# SCH_Astraeus_I_2023-09-04.net
KiCad netlist of a schematic drawn in EasyEDA
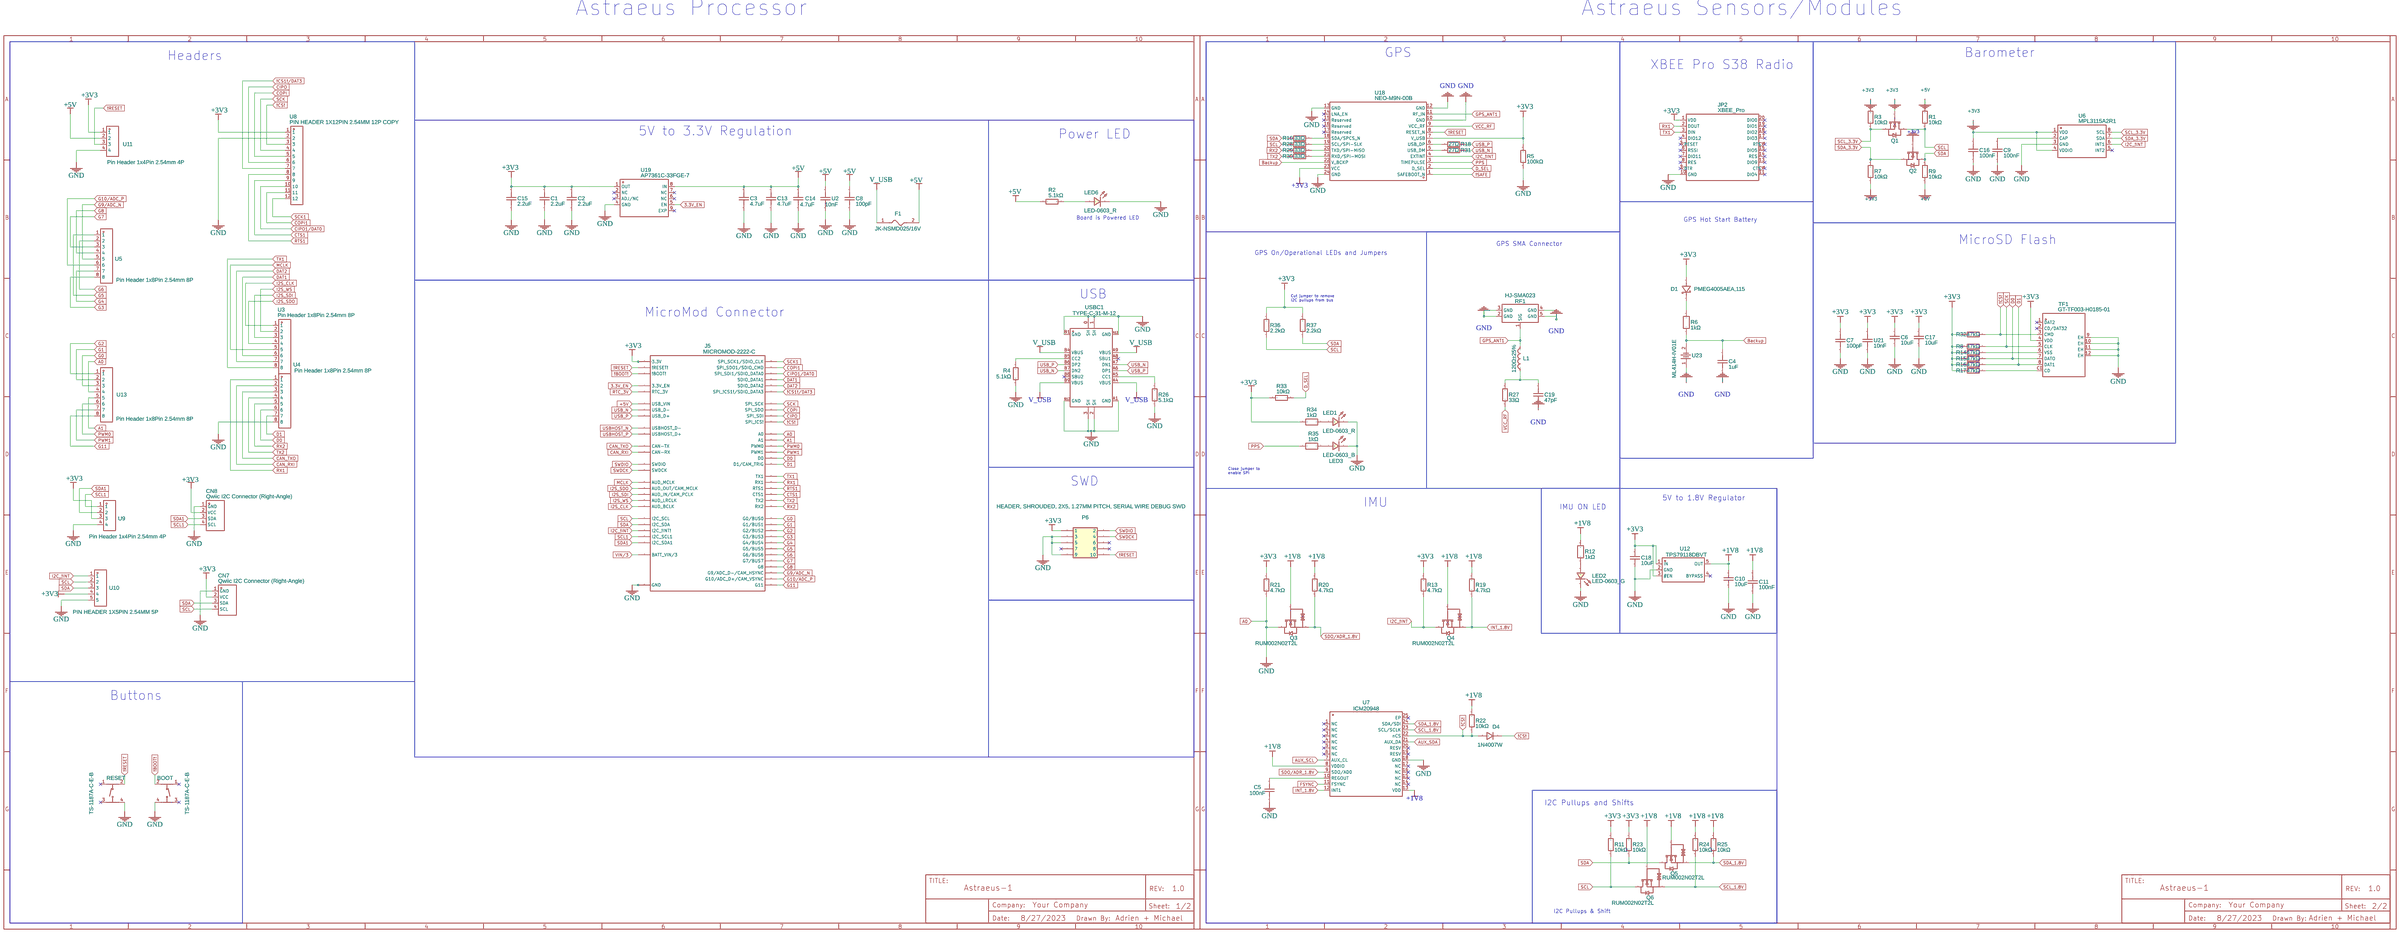
[diagram p0: schematic sheet]

(export (version "E")
  (design (tool "Eeschema 10.0.6"))
  (components
    (comp (ref "BOOT")
      (value "TS-1187A-C-E-B")
      (fields (field (name "Manufacturer") "XKB Connectivity(中国星坤)"))
      (libsource (lib "") (part "TS-1187A-C-E-B"))
    )
    (comp (ref "C1")
      (value "2.2uF")
      (fields
        (field (name "Manufacturer Part") "TCC0603X5R225K250CT")
        (field (name "Manufacturer") "CCTC(三环)")
      )
      (libsource (lib "") (part "TCC0603X5R225K250CT"))
    )
    (comp (ref "C2")
      (value "2.2uF")
      (fields
        (field (name "Manufacturer Part") "TCC0603X5R225K250CT")
        (field (name "Manufacturer") "CCTC(三环)")
      )
      (libsource (lib "") (part "TCC0603X5R225K250CT"))
    )
    (comp (ref "C3")
      (value "4.7uF")
      (fields
        (field (name "Manufacturer Part") "V475K0603X7R6R3NET")
        (field (name "Manufacturer") "VIIYONG(微容)")
      )
      (libsource (lib "") (part "V475K0603X7R6R3NET"))
    )
    (comp (ref "C4")
      (value "1uF")
      (fields (field (name "Manufacturer Part") "0603X105J160CT") (field (name "Manufacturer") "Walsin(华新科)"))
      (libsource (lib "") (part "0603X105J160CT"))
    )
    (comp (ref "C5")
      (value "100nF")
      (fields (field (name "Manufacturer Part") "0603ZC104KAT2A") (field (name "Manufacturer") "Kyocera AVX"))
      (libsource (lib "") (part "0603ZC104KAT2A"))
    )
    (comp (ref "C6")
      (value "10uF")
      (fields
        (field (name "Manufacturer Part") "CC0603MRX5R7BB106")
        (field (name "Manufacturer") "YAGEO(国巨)")
      )
      (libsource (lib "") (part "CC0603MRX5R7BB106"))
    )
    (comp (ref "C7")
      (value "100pF")
      (fields
        (field (name "Manufacturer Part") "TCC0603COG101J500CT")
        (field (name "Manufacturer") "CCTC(三环)")
      )
      (libsource (lib "") (part "TCC0603COG101J500CT"))
    )
    (comp (ref "C8")
      (value "100pF")
      (fields
        (field (name "Manufacturer Part") "TCC0603COG101J500CT")
        (field (name "Manufacturer") "CCTC(三环)")
      )
      (libsource (lib "") (part "TCC0603COG101J500CT"))
    )
    (comp (ref "C9")
      (value "100nF")
      (fields (field (name "Manufacturer Part") "0603ZC104KAT2A") (field (name "Manufacturer") "Kyocera AVX"))
      (libsource (lib "") (part "0603ZC104KAT2A"))
    )
    (comp (ref "C10")
      (value "10uF")
      (fields
        (field (name "Manufacturer Part") "CC0603MRX5R7BB106")
        (field (name "Manufacturer") "YAGEO(国巨)")
      )
      (libsource (lib "") (part "CC0603MRX5R7BB106"))
    )
    (comp (ref "C11")
      (value "100nF")
      (fields (field (name "Manufacturer Part") "0603ZC104KAT2A") (field (name "Manufacturer") "Kyocera AVX"))
      (libsource (lib "") (part "0603ZC104KAT2A"))
    )
    (comp (ref "C13")
      (value "4.7uF")
      (fields
        (field (name "Manufacturer Part") "V475K0603X7R6R3NET")
        (field (name "Manufacturer") "VIIYONG(微容)")
      )
      (libsource (lib "") (part "V475K0603X7R6R3NET"))
    )
    (comp (ref "C14")
      (value "4.7uF")
      (fields
        (field (name "Manufacturer Part") "V475K0603X7R6R3NET")
        (field (name "Manufacturer") "VIIYONG(微容)")
      )
      (libsource (lib "") (part "V475K0603X7R6R3NET"))
    )
    (comp (ref "C15")
      (value "2.2uF")
      (fields
        (field (name "Manufacturer Part") "TCC0603X5R225K250CT")
        (field (name "Manufacturer") "CCTC(三环)")
      )
      (libsource (lib "") (part "TCC0603X5R225K250CT"))
    )
    (comp (ref "C16")
      (value "100nF")
      (fields (field (name "Manufacturer Part") "0603ZC104KAT2A") (field (name "Manufacturer") "Kyocera AVX"))
      (libsource (lib "") (part "0603ZC104KAT2A"))
    )
    (comp (ref "C17")
      (value "10uF")
      (fields
        (field (name "Manufacturer Part") "CC0603MRX5R7BB106")
        (field (name "Manufacturer") "YAGEO(国巨)")
      )
      (libsource (lib "") (part "CC0603MRX5R7BB106"))
    )
    (comp (ref "C18")
      (value "10uF")
      (fields
        (field (name "Manufacturer Part") "CC0603MRX5R7BB106")
        (field (name "Manufacturer") "YAGEO(国巨)")
      )
      (libsource (lib "") (part "CC0603MRX5R7BB106"))
    )
    (comp (ref "C19")
      (value "47pF")
      (fields (field (name "Manufacturer Part") "0603CG470G500NT") (field (name "Manufacturer") "FH(风华)"))
      (libsource (lib "") (part "0603CG470G500NT"))
    )
    (comp (ref "CN7")
      (value "Qwiic I2C Connector (Right-Angle)")
      (libsource (lib "") (part "Qwiic I2C Connector (Right-Angle)"))
    )
    (comp (ref "CN8")
      (value "Qwiic I2C Connector (Right-Angle)")
      (libsource (lib "") (part "Qwiic I2C Connector (Right-Angle)"))
    )
    (comp (ref "D1")
      (value "PMEG4005AEA,115")
      (fields (field (name "Manufacturer") "Nexperia(安世)"))
      (libsource (lib "") (part "PMEG4005AEA,115"))
    )
    (comp (ref "D4")
      (value "1N4007W")
      (fields (field (name "Manufacturer") "BLUE ROCKET"))
      (libsource (lib "") (part "1N4007W"))
    )
    (comp (ref "F1")
      (value "JK-NSMD025/16V")
      (fields (field (name "Manufacturer Part") "JK-nSMD025/16V") (field (name "Manufacturer") "JK(金科)"))
      (libsource (lib "") (part "JK-NSMD025/16V"))
    )
    (comp (ref "J5") (value "MICROMOD-2222-C") (libsource (lib "") (part "MICROMOD-2222-C")))
    (comp (ref "JP2") (value "XBEE_Pro") (libsource (lib "") (part "XBEE_Pro")))
    (comp (ref "L1")
      (value "120Ω±25%")
      (fields (field (name "Manufacturer Part") "BLM18KG121TN1D") (field (name "Manufacturer") "muRata(村田)"))
      (libsource (lib "") (part "BLM18KG121TN1D"))
    )
    (comp (ref "LED1")
      (value "LED-0603_R")
      (fields
        (field (name "Manufacturer Part") "19-217/R6C-AL1M2VY/3T")
        (field (name "Manufacturer") "EVERLIGHT(台湾亿光)")
      )
      (libsource (lib "") (part "LED-0603_R"))
    )
    (comp (ref "LED2")
      (value "LED-0603_G")
      (fields
        (field (name "Manufacturer Part") "19-217/GHC-YR1S2/3T")
        (field (name "Manufacturer") "EVERLIGHT(台湾亿光)")
      )
      (libsource (lib "") (part "LED-0603_G"))
    )
    (comp (ref "LED3")
      (value "LED-0603_B")
      (fields
        (field (name "Manufacturer Part") "19-217/BHC-ZL1M2RY/3T")
        (field (name "Manufacturer") "EVERLIGHT(台湾亿光)")
      )
      (libsource (lib "") (part "LED-0603_B"))
    )
    (comp (ref "LED6")
      (value "LED-0603_R")
      (fields
        (field (name "Manufacturer Part") "19-217/R6C-AL1M2VY/3T")
        (field (name "Manufacturer") "EVERLIGHT(台湾亿光)")
      )
      (libsource (lib "") (part "LED-0603_R"))
    )
    (comp (ref "P6")
      (value "HEADER, SHROUDED, 2X5, 1.27MM PITCH, SERIAL WIRE DEBUG SWD")
      (fields (field (name "Manufacturer Part") "3220-10-0100-00") (field (name "Manufacturer") "CNC Tech"))
      (libsource (lib "") (part "HEADER, SHROUDED, 2X5, 1.27MM PITCH, SERIAL WIRE DEBUG SWD"))
    )
    (comp (ref "Q1")
      (value "BSS138_C489349")
      (fields (field (name "Manufacturer Part") "BSS138") (field (name "Manufacturer") "KEXIN(科信)"))
      (libsource (lib "") (part "BSS138_C489349"))
    )
    (comp (ref "Q2")
      (value "BSS138_C489349")
      (fields (field (name "Manufacturer Part") "BSS138") (field (name "Manufacturer") "KEXIN(科信)"))
      (libsource (lib "") (part "BSS138_C489349"))
    )
    (comp (ref "Q3")
      (value "RUM002N02T2L")
      (fields (field (name "Manufacturer") "ROHM(罗姆)"))
      (libsource (lib "") (part "RUM002N02T2L"))
    )
    (comp (ref "Q4")
      (value "RUM002N02T2L")
      (fields (field (name "Manufacturer") "ROHM(罗姆)"))
      (libsource (lib "") (part "RUM002N02T2L"))
    )
    (comp (ref "Q5")
      (value "RUM002N02T2L")
      (fields (field (name "Manufacturer") "ROHM(罗姆)"))
      (libsource (lib "") (part "RUM002N02T2L"))
    )
    (comp (ref "Q6")
      (value "RUM002N02T2L")
      (fields (field (name "Manufacturer") "ROHM(罗姆)"))
      (libsource (lib "") (part "RUM002N02T2L"))
    )
    (comp (ref "R1")
      (value "10kΩ")
      (fields (field (name "Manufacturer Part") "RMC060310K5%N") (field (name "Manufacturer") "Tyohm(幸亚电阻)"))
      (libsource (lib "") (part "RMC060310K5%N_1"))
    )
    (comp (ref "R2")
      (value "5.1kΩ")
      (fields (field (name "Manufacturer Part") "RMC06035.1K5%N") (field (name "Manufacturer") "Tyohm(幸亚电阻)"))
      (libsource (lib "") (part "RMC06035.1K5%N"))
    )
    (comp (ref "R3")
      (value "10kΩ")
      (fields (field (name "Manufacturer Part") "RMC060310K5%N") (field (name "Manufacturer") "Tyohm(幸亚电阻)"))
      (libsource (lib "") (part "RMC060310K5%N_1"))
    )
    (comp (ref "R4")
      (value "5.1kΩ")
      (fields (field (name "Manufacturer Part") "RMC06035.1K5%N") (field (name "Manufacturer") "Tyohm(幸亚电阻)"))
      (libsource (lib "") (part "RMC06035.1K5%N_1"))
    )
    (comp (ref "R5")
      (value "100kΩ")
      (fields (field (name "Manufacturer Part") "RT0603DRE07100KL") (field (name "Manufacturer") "YAGEO(国巨)"))
      (libsource (lib "") (part "RT0603DRE07100KL"))
    )
    (comp (ref "R6")
      (value "1kΩ")
      (fields (field (name "Manufacturer Part") "SCR0603J1K") (field (name "Manufacturer") "VO(翔胜)"))
      (libsource (lib "") (part "SCR0603J1K"))
    )
    (comp (ref "R7")
      (value "10kΩ")
      (fields (field (name "Manufacturer Part") "RMC060310K5%N") (field (name "Manufacturer") "Tyohm(幸亚电阻)"))
      (libsource (lib "") (part "RMC060310K5%N_1"))
    )
    (comp (ref "R8")
      (value "47kΩ")
      (fields (field (name "Manufacturer Part") "CR0603-FX-4702ELF") (field (name "Manufacturer") "BOURNS"))
      (libsource (lib "") (part "CR0603-FX-4702ELF"))
    )
    (comp (ref "R9")
      (value "10kΩ")
      (fields (field (name "Manufacturer Part") "RMC060310K5%N") (field (name "Manufacturer") "Tyohm(幸亚电阻)"))
      (libsource (lib "") (part "RMC060310K5%N_1"))
    )
    (comp (ref "R10")
      (value "33Ω")
      (fields (field (name "Manufacturer Part") "RC0603FR-0733RL") (field (name "Manufacturer") "YAGEO(国巨)"))
      (libsource (lib "") (part "RC0603FR-0733RL_2"))
    )
    (comp (ref "R11")
      (value "10kΩ")
      (fields (field (name "Manufacturer Part") "RMC060310K5%N") (field (name "Manufacturer") "Tyohm(幸亚电阻)"))
      (libsource (lib "") (part "RMC060310K5%N_1"))
    )
    (comp (ref "R12")
      (value "1kΩ")
      (fields (field (name "Manufacturer Part") "SCR0603J1K") (field (name "Manufacturer") "VO(翔胜)"))
      (libsource (lib "") (part "SCR0603J1K"))
    )
    (comp (ref "R13")
      (value "4.7kΩ")
      (fields (field (name "Manufacturer Part") "RMC06034K7FN") (field (name "Manufacturer") "Tyohm(幸亚电阻)"))
      (libsource (lib "") (part "RMC06034.7K1%N"))
    )
    (comp (ref "R14")
      (value "47kΩ")
      (fields (field (name "Manufacturer Part") "CR0603-FX-4702ELF") (field (name "Manufacturer") "BOURNS"))
      (libsource (lib "") (part "CR0603-FX-4702ELF"))
    )
    (comp (ref "R15")
      (value "47kΩ")
      (fields (field (name "Manufacturer Part") "CR0603-FX-4702ELF") (field (name "Manufacturer") "BOURNS"))
      (libsource (lib "") (part "CR0603-FX-4702ELF"))
    )
    (comp (ref "R16")
      (value "47kΩ")
      (fields (field (name "Manufacturer Part") "CR0603-FX-4702ELF") (field (name "Manufacturer") "BOURNS"))
      (libsource (lib "") (part "CR0603-FX-4702ELF"))
    )
    (comp (ref "R17")
      (value "47kΩ")
      (fields (field (name "Manufacturer Part") "CR0603-FX-4702ELF") (field (name "Manufacturer") "BOURNS"))
      (libsource (lib "") (part "CR0603-FX-4702ELF"))
    )
    (comp (ref "R18")
      (value "27Ω")
      (fields (field (name "Manufacturer Part") "CR0603FA27R0G") (field (name "Manufacturer") "LIZ(丽智电子)"))
      (libsource (lib "") (part "CR0603FA27R0G"))
    )
    (comp (ref "R19")
      (value "4.7kΩ")
      (fields (field (name "Manufacturer Part") "RMC06034K7FN") (field (name "Manufacturer") "Tyohm(幸亚电阻)"))
      (libsource (lib "") (part "RMC06034.7K1%N"))
    )
    (comp (ref "R20")
      (value "4.7kΩ")
      (fields (field (name "Manufacturer Part") "RMC06034K7FN") (field (name "Manufacturer") "Tyohm(幸亚电阻)"))
      (libsource (lib "") (part "RMC06034.7K1%N"))
    )
    (comp (ref "R21")
      (value "4.7kΩ")
      (fields (field (name "Manufacturer Part") "RMC06034K7FN") (field (name "Manufacturer") "Tyohm(幸亚电阻)"))
      (libsource (lib "") (part "RMC06034.7K1%N"))
    )
    (comp (ref "R22")
      (value "10kΩ")
      (fields (field (name "Manufacturer Part") "RMC060310K5%N") (field (name "Manufacturer") "Tyohm(幸亚电阻)"))
      (libsource (lib "") (part "RMC060310K5%N_1"))
    )
    (comp (ref "R23")
      (value "10kΩ")
      (fields (field (name "Manufacturer Part") "RMC060310K5%N") (field (name "Manufacturer") "Tyohm(幸亚电阻)"))
      (libsource (lib "") (part "RMC060310K5%N_1"))
    )
    (comp (ref "R24")
      (value "10kΩ")
      (fields (field (name "Manufacturer Part") "RMC060310K5%N") (field (name "Manufacturer") "Tyohm(幸亚电阻)"))
      (libsource (lib "") (part "RMC060310K5%N_1"))
    )
    (comp (ref "R25")
      (value "10kΩ")
      (fields (field (name "Manufacturer Part") "RMC060310K5%N") (field (name "Manufacturer") "Tyohm(幸亚电阻)"))
      (libsource (lib "") (part "RMC060310K5%N_1"))
    )
    (comp (ref "R26")
      (value "5.1kΩ")
      (fields (field (name "Manufacturer Part") "RMC06035.1K5%N") (field (name "Manufacturer") "Tyohm(幸亚电阻)"))
      (libsource (lib "") (part "RMC06035.1K5%N_2"))
    )
    (comp (ref "R27")
      (value "33Ω")
      (fields (field (name "Manufacturer Part") "RC0603FR-0733RL") (field (name "Manufacturer") "YAGEO(国巨)"))
      (libsource (lib "") (part "RC0603FR-0733RL_1"))
    )
    (comp (ref "R28")
      (value "33Ω")
      (fields (field (name "Manufacturer Part") "RC0603FR-0733RL") (field (name "Manufacturer") "YAGEO(国巨)"))
      (libsource (lib "") (part "RC0603FR-0733RL"))
    )
    (comp (ref "R29")
      (value "33Ω")
      (fields (field (name "Manufacturer Part") "RC0603FR-0733RL") (field (name "Manufacturer") "YAGEO(国巨)"))
      (libsource (lib "") (part "RC0603FR-0733RL"))
    )
    (comp (ref "R30")
      (value "33Ω")
      (fields (field (name "Manufacturer Part") "RC0603FR-0733RL") (field (name "Manufacturer") "YAGEO(国巨)"))
      (libsource (lib "") (part "RC0603FR-0733RL"))
    )
    (comp (ref "R31")
      (value "27Ω")
      (fields (field (name "Manufacturer Part") "CR0603FA27R0G") (field (name "Manufacturer") "LIZ(丽智电子)"))
      (libsource (lib "") (part "CR0603FA27R0G"))
    )
    (comp (ref "R32")
      (value "47kΩ")
      (fields (field (name "Manufacturer Part") "CR0603-FX-4702ELF") (field (name "Manufacturer") "BOURNS"))
      (libsource (lib "") (part "CR0603-FX-4702ELF"))
    )
    (comp (ref "R33")
      (value "10kΩ")
      (fields (field (name "Manufacturer Part") "RMC060310K5%N") (field (name "Manufacturer") "Tyohm(幸亚电阻)"))
      (libsource (lib "") (part "RMC060310K5%N"))
    )
    (comp (ref "R34")
      (value "1kΩ")
      (fields (field (name "Manufacturer Part") "SCR0603J1K") (field (name "Manufacturer") "VO(翔胜)"))
      (libsource (lib "") (part "SCR0603J1K_2"))
    )
    (comp (ref "R35")
      (value "1kΩ")
      (fields (field (name "Manufacturer Part") "SCR0603J1K") (field (name "Manufacturer") "VO(翔胜)"))
      (libsource (lib "") (part "SCR0603J1K_1"))
    )
    (comp (ref "R36")
      (value "2.2kΩ")
      (fields (field (name "Manufacturer Part") "RMC06032.2K5%N") (field (name "Manufacturer") "Tyohm(幸亚电阻)"))
      (libsource (lib "") (part "RMC06032.2K5%N"))
    )
    (comp (ref "R37")
      (value "2.2kΩ")
      (fields (field (name "Manufacturer Part") "RMC06032.2K5%N") (field (name "Manufacturer") "Tyohm(幸亚电阻)"))
      (libsource (lib "") (part "RMC06032.2K5%N"))
    )
    (comp (ref "RESET")
      (value "TS-1187A-C-E-B")
      (fields (field (name "Manufacturer") "XKB Connectivity(中国星坤)"))
      (libsource (lib "") (part "TS-1187A-C-E-B_1"))
    )
    (comp (ref "RF1")
      (value "HJ-SMA023")
      (fields (field (name "Manufacturer") "皇捷"))
      (libsource (lib "") (part "HJ-SMA023"))
    )
    (comp (ref "TF1")
      (value "GT-TF003-H0185-01")
      (fields (field (name "Manufacturer") "G-Switch(品赞)"))
      (libsource (lib "") (part "GT-TF003-H0185-01"))
    )
    (comp (ref "U2")
      (value "10nF")
      (fields
        (field (name "Manufacturer Part") "AC0603KRX7R7BB103")
        (field (name "Manufacturer") "YAGEO(国巨)")
      )
      (libsource (lib "") (part "AC0603KRX7R7BB103"))
    )
    (comp (ref "U3")
      (value "Pin Header 1x8Pin 2.54mm 8P")
      (libsource (lib "") (part "Pin Header 1x8Pin 2.54mm 8P"))
    )
    (comp (ref "U4")
      (value "Pin Header 1x8Pin 2.54mm 8P")
      (libsource (lib "") (part "Pin Header 1x8Pin 2.54mm 8P"))
    )
    (comp (ref "U5")
      (value "Pin Header 1x8Pin 2.54mm 8P")
      (libsource (lib "") (part "Pin Header 1x8Pin 2.54mm 8P"))
    )
    (comp (ref "U6")
      (value "MPL3115A2R1")
      (fields (field (name "Manufacturer") "NXP(恩智浦)"))
      (libsource (lib "") (part "MPL3115A2R1"))
    )
    (comp (ref "U7") (value "ICM20948") (libsource (lib "") (part "ICM20948")))
    (comp (ref "U8")
      (value "PIN HEADER 1X12PIN 2.54MM 12P COPY")
      (libsource (lib "") (part "PIN HEADER 1X12PIN 2.54MM 12P COPY"))
    )
    (comp (ref "U9")
      (value "Pin Header 1x4Pin 2.54mm 4P")
      (libsource (lib "") (part "Pin Header 1x4Pin 2.54mm 4P"))
    )
    (comp (ref "U10")
      (value "PIN HEADER 1X5PIN 2.54MM 5P")
      (libsource (lib "") (part "PIN HEADER 1X5PIN 2.54MM 5P COPY"))
    )
    (comp (ref "U11")
      (value "Pin Header 1x4Pin 2.54mm 4P")
      (libsource (lib "") (part "Pin Header 1x4Pin 2.54mm 4P"))
    )
    (comp (ref "U12")
      (value "TPS79118DBVT")
      (fields (field (name "Manufacturer") "TI(德州仪器)"))
      (libsource (lib "") (part "TPS79118DBVT"))
    )
    (comp (ref "U13")
      (value "Pin Header 1x8Pin 2.54mm 8P")
      (libsource (lib "") (part "Pin Header 1x8Pin 2.54mm 8P"))
    )
    (comp (ref "U18") (value "NEO-M9N-00B") (libsource (lib "") (part "NEO-M9N-00B")))
    (comp (ref "U19")
      (value "AP7361C-33FGE-7")
      (fields (field (name "Manufacturer") "DIODES(美台)"))
      (libsource (lib "") (part "AP7361C-33FGE-7"))
    )
    (comp (ref "U21")
      (value "10nF")
      (fields
        (field (name "Manufacturer Part") "AC0603KRX7R7BB103")
        (field (name "Manufacturer") "YAGEO(国巨)")
      )
      (libsource (lib "") (part "AC0603KRX7R7BB103"))
    )
    (comp (ref "U23")
      (value "ML414H-IV01E")
      (fields (field (name "Manufacturer") "Seiko(精工)"))
      (libsource (lib "") (part "ML414H-IV01E"))
    )
    (comp (ref "USBC1")
      (value "TYPE-C-31-M-12")
      (fields (field (name "Manufacturer") "韩国韩荣"))
      (libsource (lib "") (part "TYPE-C-31-M-12"))
    )
  )
  (nets
    (net (code "1") (name "!BOOT!") (class "Default")
      (node (ref "BOOT") (pin "2") (pinfunction "B_2") (pintype "unspecified"))
      (node (ref "J5") (pin "11") (pinfunction "!BOOT!_11") (pintype "bidirectional"))
    )
    (net (code "2") (name "!CS!") (class "Default")
      (node (ref "D4") (pin "1") (pinfunction "1_1") (pintype "unspecified"))
      (node (ref "D4") (pin "2") (pinfunction "2_2") (pintype "unspecified"))
      (node (ref "J5") (pin "55") (pinfunction "SPI_!CS!_55") (pintype "bidirectional"))
      (node (ref "R22") (pin "1") (pinfunction "1_1") (pintype "unspecified"))
      (node (ref "R32") (pin "2") (pinfunction "2_2") (pintype "unspecified"))
      (node (ref "TF1") (pin "3") (pinfunction "CMD_3") (pintype "unspecified"))
      (node (ref "U7") (pin "22") (pinfunction "nCS_22") (pintype "unspecified"))
      (node (ref "U8") (pin "3") (pinfunction "3_3") (pintype "unspecified"))
    )
    (net (code "3") (name "!CS1!{slash}DAT3") (class "Default")
      (node (ref "J5") (pin "70") (pinfunction "SPI_!CS1!/SDIO_DATA3_70") (pintype "bidirectional"))
      (node (ref "U8") (pin "7") (pinfunction "7_7") (pintype "unspecified"))
    )
    (net (code "4") (name "!RESET") (class "Default")
      (node (ref "J5") (pin "6") (pinfunction "!RESET!_6") (pintype "bidirectional"))
      (node (ref "P6") (pin "10") (pinfunction "10_10") (pintype "input"))
      (node (ref "RESET") (pin "2") (pinfunction "B_2") (pintype "unspecified"))
      (node (ref "U11") (pin "3") (pinfunction "3_3") (pintype "unspecified"))
      (node (ref "U18") (pin "8") (pinfunction "RESET_N_8") (pintype "unspecified"))
    )
    (net (code "5") (name "!SAFE") (class "Default")
      (node (ref "U18") (pin "1") (pinfunction "SAFEBOOT_N_1") (pintype "unspecified"))
    )
    (net (code "6") (name "+1V8") (class "Default")
      (node (ref "C10") (pin "2") (pinfunction "2_2") (pintype "input"))
      (node (ref "C11") (pin "2") (pinfunction "2_2") (pintype "unspecified"))
      (node (ref "Q3") (pin "1") (pinfunction "G_1") (pintype "unspecified"))
      (node (ref "Q4") (pin "1") (pinfunction "G_1") (pintype "unspecified"))
      (node (ref "Q5") (pin "1") (pinfunction "G_1") (pintype "unspecified"))
      (node (ref "Q6") (pin "1") (pinfunction "G_1") (pintype "unspecified"))
      (node (ref "R12") (pin "2") (pinfunction "2_2") (pintype "unspecified"))
      (node (ref "R19") (pin "2") (pinfunction "2_2") (pintype "unspecified"))
      (node (ref "R20") (pin "2") (pinfunction "2_2") (pintype "unspecified"))
      (node (ref "R22") (pin "2") (pinfunction "2_2") (pintype "unspecified"))
      (node (ref "R24") (pin "2") (pinfunction "2_2") (pintype "unspecified"))
      (node (ref "R25") (pin "2") (pinfunction "2_2") (pintype "unspecified"))
      (node (ref "U12") (pin "5") (pinfunction "OUT_5") (pintype "unspecified"))
      (node (ref "U7") (pin "13") (pinfunction "VDD_13") (pintype "unspecified"))
      (node (ref "U7") (pin "8") (pinfunction "VDDIO_8") (pintype "unspecified"))
    )
    (net (code "7") (name "+3V3") (class "Default")
      (node (ref "C1") (pin "2") (pinfunction "2_2") (pintype "unspecified"))
      (node (ref "C15") (pin "2") (pinfunction "2_2") (pintype "unspecified"))
      (node (ref "C16") (pin "2") (pinfunction "2_2") (pintype "unspecified"))
      (node (ref "C17") (pin "2") (pinfunction "2_2") (pintype "input"))
      (node (ref "C18") (pin "2") (pinfunction "2_2") (pintype "input"))
      (node (ref "C2") (pin "2") (pinfunction "2_2") (pintype "unspecified"))
      (node (ref "C6") (pin "2") (pinfunction "2_2") (pintype "input"))
      (node (ref "C7") (pin "1") (pinfunction "1_1") (pintype "unspecified"))
      (node (ref "CN7") (pin "2") (pinfunction "VCC_2") (pintype "unspecified"))
      (node (ref "CN8") (pin "2") (pinfunction "VCC_2") (pintype "unspecified"))
      (node (ref "D1") (pin "2") (pinfunction "2_2") (pintype "unspecified"))
      (node (ref "J5") (pin "2") (pinfunction "3.3V_2") (pintype "bidirectional"))
      (node (ref "J5") (pin "74") (pinfunction "3.3V_74") (pintype "bidirectional"))
      (node (ref "JP2") (pin "1") (pinfunction "VDD_1") (pintype "passive"))
      (node (ref "P6") (pin "1") (pinfunction "1_1") (pintype "input"))
      (node (ref "Q1") (pin "1") (pinfunction "G_1") (pintype "unspecified"))
      (node (ref "Q2") (pin "1") (pinfunction "G_1") (pintype "unspecified"))
      (node (ref "R11") (pin "2") (pinfunction "2_2") (pintype "unspecified"))
      (node (ref "R13") (pin "2") (pinfunction "2_2") (pintype "unspecified"))
      (node (ref "R14") (pin "1") (pinfunction "1_1") (pintype "unspecified"))
      (node (ref "R15") (pin "1") (pinfunction "1_1") (pintype "unspecified"))
      (node (ref "R16") (pin "1") (pinfunction "1_1") (pintype "unspecified"))
      (node (ref "R17") (pin "1") (pinfunction "1_1") (pintype "unspecified"))
      (node (ref "R21") (pin "2") (pinfunction "2_2") (pintype "unspecified"))
      (node (ref "R23") (pin "2") (pinfunction "2_2") (pintype "unspecified"))
      (node (ref "R3") (pin "2") (pinfunction "2_2") (pintype "unspecified"))
      (node (ref "R32") (pin "1") (pinfunction "1_1") (pintype "unspecified"))
      (node (ref "R33") (pin "2") (pinfunction "2_2") (pintype "unspecified"))
      (node (ref "R34") (pin "2") (pinfunction "2_2") (pintype "unspecified"))
      (node (ref "R36") (pin "2") (pinfunction "2_2") (pintype "unspecified"))
      (node (ref "R37") (pin "2") (pinfunction "2_2") (pintype "unspecified"))
      (node (ref "R5") (pin "2") (pinfunction "2_2") (pintype "unspecified"))
      (node (ref "R7") (pin "1") (pinfunction "1_1") (pintype "unspecified"))
      (node (ref "R8") (pin "1") (pinfunction "1_1") (pintype "unspecified"))
      (node (ref "TF1") (pin "4") (pinfunction "VDD_4") (pintype "unspecified"))
      (node (ref "U10") (pin "4") (pinfunction "4_4") (pintype "unspecified"))
      (node (ref "U11") (pin "1") (pinfunction "1_1") (pintype "unspecified"))
      (node (ref "U12") (pin "1") (pinfunction "IN_1") (pintype "unspecified"))
      (node (ref "U12") (pin "3") (pinfunction "#EN_3") (pintype "unspecified"))
      (node (ref "U18") (pin "23") (pinfunction "VCC_23") (pintype "unspecified"))
      (node (ref "U18") (pin "7") (pinfunction "V_USB_7") (pintype "unspecified"))
      (node (ref "U19") (pin "1") (pinfunction "OUT_1") (pintype "unspecified"))
      (node (ref "U21") (pin "2") (pinfunction "2_2") (pintype "unspecified"))
      (node (ref "U6") (pin "1") (pinfunction "VDD_1") (pintype "unspecified"))
      (node (ref "U6") (pin "4") (pinfunction "VDDIO_4") (pintype "unspecified"))
      (node (ref "U8") (pin "1") (pinfunction "1_1") (pintype "unspecified"))
      (node (ref "U9") (pin "3") (pinfunction "3_3") (pintype "unspecified"))
    )
    (net (code "8") (name "+5V") (class "Default")
      (node (ref "C13") (pin "2") (pinfunction "2_2") (pintype "unspecified"))
      (node (ref "C14") (pin "2") (pinfunction "2_2") (pintype "unspecified"))
      (node (ref "C3") (pin "2") (pinfunction "2_2") (pintype "unspecified"))
      (node (ref "C8") (pin "1") (pinfunction "1_1") (pintype "unspecified"))
      (node (ref "F1") (pin "2") (pinfunction "2_2") (pintype "unspecified"))
      (node (ref "J5") (pin "9") (pinfunction "USB_VIN_9") (pintype "bidirectional"))
      (node (ref "R1") (pin "2") (pinfunction "2_2") (pintype "unspecified"))
      (node (ref "R2") (pin "1") (pinfunction "1_1") (pintype "unspecified"))
      (node (ref "R9") (pin "1") (pinfunction "1_1") (pintype "unspecified"))
      (node (ref "U11") (pin "2") (pinfunction "2_2") (pintype "unspecified"))
      (node (ref "U19") (pin "8") (pinfunction "IN_8") (pintype "unspecified"))
      (node (ref "U2") (pin "2") (pinfunction "2_2") (pintype "unspecified"))
    )
    (net (code "9") (name "3.3V_EN") (class "Default")
      (node (ref "J5") (pin "4") (pinfunction "3.3V_EN_4") (pintype "bidirectional"))
      (node (ref "U19") (pin "5") (pinfunction "EN_5") (pintype "unspecified"))
    )
    (net (code "10") (name "A0") (class "Default")
      (node (ref "BOOT") (pin "4") (pinfunction "D_4") (pintype "unspecified"))
      (node (ref "C1") (pin "1") (pinfunction "1_1") (pintype "unspecified"))
      (node (ref "C10") (pin "1") (pinfunction "1_1") (pintype "input"))
      (node (ref "C11") (pin "1") (pinfunction "1_1") (pintype "unspecified"))
      (node (ref "C13") (pin "1") (pinfunction "1_1") (pintype "unspecified"))
      (node (ref "C14") (pin "1") (pinfunction "1_1") (pintype "unspecified"))
      (node (ref "C15") (pin "1") (pinfunction "1_1") (pintype "unspecified"))
      (node (ref "C16") (pin "1") (pinfunction "1_1") (pintype "unspecified"))
      (node (ref "C17") (pin "1") (pinfunction "1_1") (pintype "input"))
      (node (ref "C18") (pin "1") (pinfunction "1_1") (pintype "input"))
      (node (ref "C19") (pin "2") (pinfunction "2_2") (pintype "unspecified"))
      (node (ref "C2") (pin "1") (pinfunction "1_1") (pintype "unspecified"))
      (node (ref "C3") (pin "1") (pinfunction "1_1") (pintype "unspecified"))
      (node (ref "C4") (pin "1") (pinfunction "1_1") (pintype "unspecified"))
      (node (ref "C5") (pin "1") (pinfunction "1_1") (pintype "unspecified"))
      (node (ref "C6") (pin "1") (pinfunction "1_1") (pintype "input"))
      (node (ref "C7") (pin "2") (pinfunction "2_2") (pintype "unspecified"))
      (node (ref "C8") (pin "2") (pinfunction "2_2") (pintype "unspecified"))
      (node (ref "C9") (pin "1") (pinfunction "1_1") (pintype "unspecified"))
      (node (ref "CN7") (pin "1") (pinfunction "GND_1") (pintype "unspecified"))
      (node (ref "CN8") (pin "1") (pinfunction "GND_1") (pintype "unspecified"))
      (node (ref "J5") (pin "1") (pinfunction "GND_1") (pintype "bidirectional"))
      (node (ref "J5") (pin "33") (pinfunction "GND_33") (pintype "bidirectional"))
      (node (ref "J5") (pin "34") (pinfunction "A0_34") (pintype "bidirectional"))
      (node (ref "J5") (pin "36") (pinfunction "GND_36") (pintype "bidirectional"))
      (node (ref "J5") (pin "39") (pinfunction "GND_39") (pintype "bidirectional"))
      (node (ref "J5") (pin "45") (pinfunction "GND_45") (pintype "bidirectional"))
      (node (ref "J5") (pin "7") (pinfunction "GND_7") (pintype "bidirectional"))
      (node (ref "J5") (pin "75") (pinfunction "GND_75") (pintype "bidirectional"))
      (node (ref "JP2") (pin "10") (pinfunction "GND_10") (pintype "passive"))
      (node (ref "LED1") (pin "2") (pinfunction "2_2") (pintype "unspecified"))
      (node (ref "LED2") (pin "2") (pinfunction "2_2") (pintype "unspecified"))
      (node (ref "LED3") (pin "2") (pinfunction "2_2") (pintype "unspecified"))
      (node (ref "LED6") (pin "2") (pinfunction "2_2") (pintype "unspecified"))
      (node (ref "P6") (pin "3") (pinfunction "3_3") (pintype "input"))
      (node (ref "P6") (pin "5") (pinfunction "5_5") (pintype "input"))
      (node (ref "P6") (pin "9") (pinfunction "9_9") (pintype "input"))
      (node (ref "Q3") (pin "3") (pinfunction "D_3") (pintype "unspecified"))
      (node (ref "R21") (pin "1") (pinfunction "1_1") (pintype "unspecified"))
      (node (ref "R26") (pin "1") (pinfunction "1_1") (pintype "unspecified"))
      (node (ref "R4") (pin "2") (pinfunction "2_2") (pintype "unspecified"))
      (node (ref "R5") (pin "1") (pinfunction "1_1") (pintype "unspecified"))
      (node (ref "RESET") (pin "4") (pinfunction "D_4") (pintype "unspecified"))
      (node (ref "RF1") (pin "2") (pinfunction "GND_2") (pintype "unspecified"))
      (node (ref "RF1") (pin "3") (pinfunction "GND_3") (pintype "unspecified"))
      (node (ref "RF1") (pin "4") (pinfunction "GND_4") (pintype "unspecified"))
      (node (ref "RF1") (pin "5") (pinfunction "GND_5") (pintype "unspecified"))
      (node (ref "TF1") (pin "10") (pinfunction "EH_10") (pintype "unspecified"))
      (node (ref "TF1") (pin "11") (pinfunction "EH_11") (pintype "unspecified"))
      (node (ref "TF1") (pin "12") (pinfunction "EH_12") (pintype "unspecified"))
      (node (ref "TF1") (pin "9") (pinfunction "EH_9") (pintype "unspecified"))
      (node (ref "U10") (pin "5") (pinfunction "5_5") (pintype "unspecified"))
      (node (ref "U11") (pin "4") (pinfunction "4_4") (pintype "unspecified"))
      (node (ref "U12") (pin "2") (pinfunction "GND_2") (pintype "unspecified"))
      (node (ref "U13") (pin "4") (pinfunction "4_4") (pintype "unspecified"))
      (node (ref "U18") (pin "10") (pinfunction "GND_10") (pintype "unspecified"))
      (node (ref "U18") (pin "12") (pinfunction "GND_12") (pintype "unspecified"))
      (node (ref "U18") (pin "13") (pinfunction "GND_13") (pintype "unspecified"))
      (node (ref "U18") (pin "24") (pinfunction "GND_24") (pintype "unspecified"))
      (node (ref "U19") (pin "4") (pinfunction "GND_4") (pintype "unspecified"))
      (node (ref "U2") (pin "1") (pinfunction "1_1") (pintype "unspecified"))
      (node (ref "U21") (pin "1") (pinfunction "1_1") (pintype "unspecified"))
      (node (ref "U23") (pin "1") (pinfunction "1_1") (pintype "input"))
      (node (ref "U4") (pin "8") (pinfunction "8_8") (pintype "unspecified"))
      (node (ref "U6") (pin "3") (pinfunction "GND_3") (pintype "unspecified"))
      (node (ref "U7") (pin "18") (pinfunction "GND_18") (pintype "unspecified"))
      (node (ref "U8") (pin "2") (pinfunction "2_2") (pintype "unspecified"))
      (node (ref "U9") (pin "4") (pinfunction "4_4") (pintype "unspecified"))
      (node (ref "USBC1") (pin "0") (pinfunction "SH_0") (pintype "unspecified"))
      (node (ref "USBC1") (pin "1") (pinfunction "SH_1") (pintype "unspecified"))
      (node (ref "USBC1") (pin "2") (pinfunction "SH_2") (pintype "unspecified"))
      (node (ref "USBC1") (pin "3") (pinfunction "SH_3") (pintype "unspecified"))
      (node (ref "USBC1") (pin "A1") (pinfunction "GND_A1") (pintype "unspecified"))
      (node (ref "USBC1") (pin "A12") (pinfunction "GND_A12") (pintype "unspecified"))
      (node (ref "USBC1") (pin "B1") (pinfunction "GND_B1") (pintype "unspecified"))
      (node (ref "USBC1") (pin "B12") (pinfunction "GND_B12") (pintype "unspecified"))
    )
    (net (code "11") (name "A1") (class "Default")
      (node (ref "J5") (pin "38") (pinfunction "A1_38") (pintype "bidirectional"))
      (node (ref "U13") (pin "5") (pinfunction "5_5") (pintype "unspecified"))
    )
    (net (code "12") (name "AUX_SCL") (class "Default")
      (node (ref "U7") (pin "7") (pinfunction "AUX_CL_7") (pintype "unspecified"))
    )
    (net (code "13") (name "AUX_SDA") (class "Default")
      (node (ref "U7") (pin "21") (pinfunction "AUX_DA_21") (pintype "unspecified"))
    )
    (net (code "14") (name "Backup") (class "Default")
      (node (ref "C4") (pin "2") (pinfunction "2_2") (pintype "unspecified"))
      (node (ref "R6") (pin "1") (pinfunction "1_1") (pintype "unspecified"))
      (node (ref "U18") (pin "22") (pinfunction "V_BCKP_22") (pintype "unspecified"))
      (node (ref "U23") (pin "2") (pinfunction "2_2") (pintype "input"))
    )
    (net (code "15") (name "CAN_RXI") (class "Default")
      (node (ref "J5") (pin "41") (pinfunction "CAN-RX_41") (pintype "bidirectional"))
      (node (ref "U4") (pin "2") (pinfunction "2_2") (pintype "unspecified"))
    )
    (net (code "16") (name "CAN_TXO") (class "Default")
      (node (ref "J5") (pin "43") (pinfunction "CAN-TX_43") (pintype "bidirectional"))
      (node (ref "U4") (pin "3") (pinfunction "3_3") (pintype "unspecified"))
    )
    (net (code "17") (name "CIPO") (class "Default")
      (node (ref "J5") (pin "61") (pinfunction "SPI_SDI_61") (pintype "bidirectional"))
      (node (ref "U8") (pin "6") (pinfunction "6_6") (pintype "unspecified"))
    )
    (net (code "18") (name "CIPO1{slash}DAT0") (class "Default")
      (node (ref "J5") (pin "64") (pinfunction "SPI_SDI1/SDIO_DATA0_64") (pintype "bidirectional"))
      (node (ref "U8") (pin "10") (pinfunction "10_10") (pintype "unspecified"))
    )
    (net (code "19") (name "COPI") (class "Default")
      (node (ref "J5") (pin "59") (pinfunction "SPI_SDO_59") (pintype "bidirectional"))
      (node (ref "U8") (pin "5") (pinfunction "5_5") (pintype "unspecified"))
    )
    (net (code "20") (name "COPI1") (class "Default")
      (node (ref "J5") (pin "62") (pinfunction "SPI_SDO1/SDIO_CMD_62") (pintype "bidirectional"))
      (node (ref "U8") (pin "11") (pinfunction "11_11") (pintype "unspecified"))
    )
    (net (code "21") (name "CTS1") (class "Default")
      (node (ref "J5") (pin "15") (pinfunction "CTS1_15") (pintype "bidirectional"))
      (node (ref "U8") (pin "9") (pinfunction "9_9") (pintype "unspecified"))
    )
    (net (code "22") (name "D0") (class "Default")
      (node (ref "J5") (pin "10") (pinfunction "D0_10") (pintype "bidirectional"))
      (node (ref "R15") (pin "2") (pinfunction "2_2") (pintype "unspecified"))
      (node (ref "TF1") (pin "7") (pinfunction "DATO_7") (pintype "unspecified"))
      (node (ref "U4") (pin "6") (pinfunction "6_6") (pintype "unspecified"))
    )
    (net (code "23") (name "D1") (class "Default")
      (node (ref "J5") (pin "18") (pinfunction "D1/CAM_TRIG_18") (pintype "bidirectional"))
      (node (ref "R16") (pin "2") (pinfunction "2_2") (pintype "unspecified"))
      (node (ref "TF1") (pin "8") (pinfunction "DAT1_8") (pintype "unspecified"))
      (node (ref "U4") (pin "7") (pinfunction "7_7") (pintype "unspecified"))
    )
    (net (code "24") (name "DAT1") (class "Default")
      (node (ref "J5") (pin "66") (pinfunction "SDIO_DATA1_66") (pintype "bidirectional"))
      (node (ref "U3") (pin "6") (pinfunction "6_6") (pintype "unspecified"))
    )
    (net (code "25") (name "DAT2") (class "Default")
      (node (ref "J5") (pin "68") (pinfunction "SDIO_DATA2_68") (pintype "bidirectional"))
      (node (ref "U3") (pin "7") (pinfunction "7_7") (pintype "unspecified"))
    )
    (net (code "26") (name "D_SEL") (class "Default")
      (node (ref "R33") (pin "1") (pinfunction "1_1") (pintype "unspecified"))
      (node (ref "U18") (pin "2") (pinfunction "D_SEL_2") (pintype "unspecified"))
    )
    (net (code "27") (name "FSYNC") (class "Default")
      (node (ref "U7") (pin "11") (pinfunction "FSYNC_11") (pintype "unspecified"))
    )
    (net (code "28") (name "G0") (class "Default")
      (node (ref "J5") (pin "40") (pinfunction "G0/BUS0_40") (pintype "bidirectional"))
      (node (ref "U13") (pin "3") (pinfunction "3_3") (pintype "unspecified"))
    )
    (net (code "29") (name "G1") (class "Default")
      (node (ref "J5") (pin "42") (pinfunction "G1/BUS1_42") (pintype "bidirectional"))
      (node (ref "U13") (pin "2") (pinfunction "2_2") (pintype "unspecified"))
    )
    (net (code "30") (name "G2") (class "Default")
      (node (ref "J5") (pin "44") (pinfunction "G2/BUS2_44") (pintype "bidirectional"))
      (node (ref "U13") (pin "1") (pinfunction "1_1") (pintype "unspecified"))
    )
    (net (code "31") (name "G3") (class "Default")
      (node (ref "J5") (pin "46") (pinfunction "G3/BUS3_46") (pintype "bidirectional"))
      (node (ref "U5") (pin "8") (pinfunction "8_8") (pintype "unspecified"))
    )
    (net (code "32") (name "G4") (class "Default")
      (node (ref "J5") (pin "48") (pinfunction "G4/BUS4_48") (pintype "bidirectional"))
      (node (ref "U5") (pin "7") (pinfunction "7_7") (pintype "unspecified"))
    )
    (net (code "33") (name "G5") (class "Default")
      (node (ref "J5") (pin "73") (pinfunction "G5/BUS5_73") (pintype "bidirectional"))
      (node (ref "U5") (pin "1") (pinfunction "1_1") (pintype "unspecified"))
    )
    (net (code "34") (name "G6") (class "Default")
      (node (ref "J5") (pin "71") (pinfunction "G6/BUS6_71") (pintype "bidirectional"))
      (node (ref "U5") (pin "2") (pinfunction "2_2") (pintype "unspecified"))
    )
    (net (code "35") (name "G7") (class "Default")
      (node (ref "J5") (pin "69") (pinfunction "G7/BUS7_69") (pintype "bidirectional"))
      (node (ref "U5") (pin "3") (pinfunction "3_3") (pintype "unspecified"))
    )
    (net (code "36") (name "G8") (class "Default")
      (node (ref "J5") (pin "67") (pinfunction "G8_67") (pintype "bidirectional"))
      (node (ref "U5") (pin "4") (pinfunction "4_4") (pintype "unspecified"))
    )
    (net (code "37") (name "G9{slash}ADC_N") (class "Default")
      (node (ref "J5") (pin "65") (pinfunction "G9/ADC_D-/CAM_HSYNC_65") (pintype "bidirectional"))
      (node (ref "U5") (pin "5") (pinfunction "5_5") (pintype "unspecified"))
    )
    (net (code "38") (name "G10{slash}ADC_P") (class "Default")
      (node (ref "J5") (pin "63") (pinfunction "G10/ADC_D+/CAM_VSYNC_63") (pintype "bidirectional"))
      (node (ref "U5") (pin "6") (pinfunction "6_6") (pintype "unspecified"))
    )
    (net (code "39") (name "G11") (class "Default")
      (node (ref "J5") (pin "8") (pinfunction "G11_8") (pintype "bidirectional"))
      (node (ref "U13") (pin "8") (pinfunction "8_8") (pintype "unspecified"))
    )
    (net (code "40") (name "GPS_ANT1") (class "Default")
      (node (ref "L1") (pin "2") (pinfunction "2_2") (pintype "unspecified"))
      (node (ref "RF1") (pin "1") (pinfunction "SIG_1") (pintype "unspecified"))
      (node (ref "U18") (pin "11") (pinfunction "RF_IN_11") (pintype "unspecified"))
    )
    (net (code "41") (name "I2C_!INT") (class "Default")
      (node (ref "J5") (pin "16") (pinfunction "I2C_!INT!_16") (pintype "bidirectional"))
      (node (ref "Q4") (pin "3") (pinfunction "D_3") (pintype "unspecified"))
      (node (ref "R13") (pin "1") (pinfunction "1_1") (pintype "unspecified"))
      (node (ref "U10") (pin "1") (pinfunction "1_1") (pintype "unspecified"))
      (node (ref "U18") (pin "4") (pinfunction "EXTINT_4") (pintype "unspecified"))
      (node (ref "U6") (pin "6") (pinfunction "INT1_6") (pintype "unspecified"))
    )
    (net (code "42") (name "I2S_CLK") (class "Default")
      (node (ref "J5") (pin "50") (pinfunction "AUD_BCLK_50") (pintype "bidirectional"))
      (node (ref "U3") (pin "1") (pinfunction "1_1") (pintype "unspecified"))
    )
    (net (code "43") (name "I2S_SDI") (class "Default")
      (node (ref "J5") (pin "54") (pinfunction "AUD_IN/CAM_PCLK_54") (pintype "bidirectional"))
      (node (ref "U3") (pin "3") (pinfunction "3_3") (pintype "unspecified"))
    )
    (net (code "44") (name "I2S_SDO") (class "Default")
      (node (ref "J5") (pin "56") (pinfunction "AUD_OUT/CAM_MCLK_56") (pintype "bidirectional"))
      (node (ref "U3") (pin "4") (pinfunction "4_4") (pintype "unspecified"))
    )
    (net (code "45") (name "I2S_WS") (class "Default")
      (node (ref "J5") (pin "52") (pinfunction "AUD_LRCLK_52") (pintype "bidirectional"))
      (node (ref "U3") (pin "2") (pinfunction "2_2") (pintype "unspecified"))
    )
    (net (code "46") (name "INT_1.8V") (class "Default")
      (node (ref "Q4") (pin "2") (pinfunction "S_2") (pintype "unspecified"))
      (node (ref "R19") (pin "1") (pinfunction "1_1") (pintype "unspecified"))
      (node (ref "U7") (pin "12") (pinfunction "INT1_12") (pintype "unspecified"))
    )
    (net (code "47") (name "MCLK") (class "Default")
      (node (ref "J5") (pin "58") (pinfunction "AUD_MCLK_58") (pintype "bidirectional"))
      (node (ref "U3") (pin "5") (pinfunction "5_5") (pintype "unspecified"))
    )
    (net (code "48") (name "Net-(C19-Pad1)") (class "Default")
      (node (ref "C19") (pin "1") (pinfunction "1_1") (pintype "unspecified"))
      (node (ref "L1") (pin "1") (pinfunction "1_1") (pintype "unspecified"))
      (node (ref "R27") (pin "2") (pinfunction "2_2") (pintype "input"))
    )
    (net (code "49") (name "Net-(D1-Pad1)") (class "Default")
      (node (ref "D1") (pin "1") (pinfunction "1_1") (pintype "unspecified"))
      (node (ref "R6") (pin "2") (pinfunction "2_2") (pintype "unspecified"))
    )
    (net (code "50") (name "Net-(LED1-Pad1)") (class "Default")
      (node (ref "LED1") (pin "1") (pinfunction "1_1") (pintype "unspecified"))
      (node (ref "R34") (pin "1") (pinfunction "1_1") (pintype "unspecified"))
    )
    (net (code "51") (name "Net-(LED2-Pad1)") (class "Default")
      (node (ref "LED2") (pin "1") (pinfunction "1_1") (pintype "unspecified"))
      (node (ref "R12") (pin "1") (pinfunction "1_1") (pintype "unspecified"))
    )
    (net (code "52") (name "Net-(LED3-Pad1)") (class "Default")
      (node (ref "LED3") (pin "1") (pinfunction "1_1") (pintype "unspecified"))
      (node (ref "R35") (pin "2") (pinfunction "2_2") (pintype "unspecified"))
    )
    (net (code "53") (name "Net-(LED6-Pad1)") (class "Default")
      (node (ref "LED6") (pin "1") (pinfunction "1_1") (pintype "unspecified"))
      (node (ref "R2") (pin "2") (pinfunction "2_2") (pintype "unspecified"))
    )
    (net (code "54") (name "Net-(R17-Pad2)") (class "Default")
      (node (ref "R17") (pin "2") (pinfunction "2_2") (pintype "unspecified"))
      (node (ref "TF1") (pin "CD") (pinfunction "CD_CD") (pintype "unspecified"))
    )
    (net (code "55") (name "Net-(TF1-VSS)") (class "Default")
      (node (ref "R14") (pin "2") (pinfunction "2_2") (pintype "unspecified"))
      (node (ref "TF1") (pin "6") (pinfunction "VSS_6") (pintype "unspecified"))
    )
    (net (code "56") (name "Net-(U6-CAP)") (class "Default")
      (node (ref "C9") (pin "2") (pinfunction "2_2") (pintype "unspecified"))
      (node (ref "U6") (pin "2") (pinfunction "CAP_2") (pintype "unspecified"))
    )
    (net (code "57") (name "Net-(U7-REGOUT)") (class "Default")
      (node (ref "C5") (pin "2") (pinfunction "2_2") (pintype "unspecified"))
      (node (ref "U7") (pin "10") (pinfunction "REGOUT_10") (pintype "unspecified"))
    )
    (net (code "58") (name "Net-(U18-RXD{slash}SPI-MOSI)") (class "Default")
      (node (ref "R30") (pin "1") (pinfunction "1_1") (pintype "input"))
      (node (ref "U18") (pin "21") (pinfunction "RXD/SPI-MOSI_21") (pintype "unspecified"))
    )
    (net (code "59") (name "Net-(U18-SCL{slash}SPI-SLK)") (class "Default")
      (node (ref "R28") (pin "1") (pinfunction "1_1") (pintype "input"))
      (node (ref "U18") (pin "19") (pinfunction "SCL/SPI-SLK_19") (pintype "unspecified"))
    )
    (net (code "60") (name "Net-(U18-SDA{slash}SPCS_N)") (class "Default")
      (node (ref "R10") (pin "2") (pinfunction "2_2") (pintype "input"))
      (node (ref "U18") (pin "18") (pinfunction "SDA/SPCS_N_18") (pintype "unspecified"))
    )
    (net (code "61") (name "Net-(U18-TXD{slash}SPI-MISO)") (class "Default")
      (node (ref "R29") (pin "1") (pinfunction "1_1") (pintype "input"))
      (node (ref "U18") (pin "20") (pinfunction "TXD/SPI-MISO_20") (pintype "unspecified"))
    )
    (net (code "62") (name "Net-(U18-USB_DM)") (class "Default")
      (node (ref "R31") (pin "1") (pinfunction "1_1") (pintype "input"))
      (node (ref "U18") (pin "5") (pinfunction "USB_DM_5") (pintype "unspecified"))
    )
    (net (code "63") (name "Net-(U18-USB_DP)") (class "Default")
      (node (ref "R18") (pin "1") (pinfunction "1_1") (pintype "input"))
      (node (ref "U18") (pin "6") (pinfunction "USB_DP_6") (pintype "unspecified"))
    )
    (net (code "64") (name "Net-(USBC1-CC1)") (class "Default")
      (node (ref "R26") (pin "2") (pinfunction "2_2") (pintype "unspecified"))
      (node (ref "USBC1") (pin "A5") (pinfunction "CC1_A5") (pintype "unspecified"))
    )
    (net (code "65") (name "Net-(USBC1-CC2)") (class "Default")
      (node (ref "R4") (pin "1") (pinfunction "1_1") (pintype "unspecified"))
      (node (ref "USBC1") (pin "B5") (pinfunction "CC2_B5") (pintype "unspecified"))
    )
    (net (code "66") (name "PPS") (class "Default")
      (node (ref "R35") (pin "1") (pinfunction "1_1") (pintype "unspecified"))
      (node (ref "U18") (pin "3") (pinfunction "TIMEPULSE_3") (pintype "unspecified"))
    )
    (net (code "67") (name "PWM0") (class "Default")
      (node (ref "J5") (pin "32") (pinfunction "PWM0_32") (pintype "bidirectional"))
      (node (ref "U13") (pin "6") (pinfunction "6_6") (pintype "unspecified"))
    )
    (net (code "68") (name "PWM1") (class "Default")
      (node (ref "J5") (pin "47") (pinfunction "PWM1_47") (pintype "bidirectional"))
      (node (ref "U13") (pin "7") (pinfunction "7_7") (pintype "unspecified"))
    )
    (net (code "69") (name "RTC_3V") (class "Default")
      (node (ref "J5") (pin "72") (pinfunction "RTC_3V_72") (pintype "bidirectional"))
    )
    (net (code "70") (name "RTS1") (class "Default")
      (node (ref "J5") (pin "13") (pinfunction "RTS1_13") (pintype "bidirectional"))
      (node (ref "U8") (pin "8") (pinfunction "8_8") (pintype "unspecified"))
    )
    (net (code "71") (name "RX1") (class "Default")
      (node (ref "J5") (pin "19") (pinfunction "RX1_19") (pintype "bidirectional"))
      (node (ref "JP2") (pin "2") (pinfunction "DOUT_2") (pintype "output"))
      (node (ref "U4") (pin "1") (pinfunction "1_1") (pintype "unspecified"))
    )
    (net (code "72") (name "RX2") (class "Default")
      (node (ref "J5") (pin "20") (pinfunction "RX2_20") (pintype "bidirectional"))
      (node (ref "R29") (pin "2") (pinfunction "2_2") (pintype "input"))
      (node (ref "U4") (pin "5") (pinfunction "5_5") (pintype "unspecified"))
    )
    (net (code "73") (name "SCK") (class "Default")
      (node (ref "J5") (pin "57") (pinfunction "SPI_SCK_57") (pintype "bidirectional"))
      (node (ref "R8") (pin "2") (pinfunction "2_2") (pintype "unspecified"))
      (node (ref "TF1") (pin "5") (pinfunction "CLK_5") (pintype "unspecified"))
      (node (ref "U8") (pin "4") (pinfunction "4_4") (pintype "unspecified"))
    )
    (net (code "74") (name "SCK1") (class "Default")
      (node (ref "J5") (pin "60") (pinfunction "SPI_SCK1/SDIO_CLK_60") (pintype "bidirectional"))
      (node (ref "U8") (pin "12") (pinfunction "12_12") (pintype "unspecified"))
    )
    (net (code "75") (name "SCL") (class "Default")
      (node (ref "CN7") (pin "4") (pinfunction "SCL_4") (pintype "unspecified"))
      (node (ref "J5") (pin "14") (pinfunction "I2C_SCL_14") (pintype "bidirectional"))
      (node (ref "Q1") (pin "3") (pinfunction "D_3") (pintype "unspecified"))
      (node (ref "Q6") (pin "3") (pinfunction "D_3") (pintype "unspecified"))
      (node (ref "R1") (pin "1") (pinfunction "1_1") (pintype "unspecified"))
      (node (ref "R11") (pin "1") (pinfunction "1_1") (pintype "unspecified"))
      (node (ref "R28") (pin "2") (pinfunction "2_2") (pintype "input"))
      (node (ref "R36") (pin "1") (pinfunction "1_1") (pintype "unspecified"))
      (node (ref "U10") (pin "2") (pinfunction "2_2") (pintype "unspecified"))
    )
    (net (code "76") (name "SCL1") (class "Default")
      (node (ref "CN8") (pin "4") (pinfunction "SCL_4") (pintype "unspecified"))
      (node (ref "J5") (pin "53") (pinfunction "I2C_SCL1_53") (pintype "bidirectional"))
      (node (ref "U9") (pin "1") (pinfunction "1_1") (pintype "unspecified"))
    )
    (net (code "77") (name "SCL_1.8V") (class "Default")
      (node (ref "Q6") (pin "2") (pinfunction "S_2") (pintype "unspecified"))
      (node (ref "R24") (pin "1") (pinfunction "1_1") (pintype "unspecified"))
      (node (ref "U7") (pin "23") (pinfunction "SCL/SCLK_23") (pintype "unspecified"))
    )
    (net (code "78") (name "SCL_3.3V") (class "Default")
      (node (ref "Q1") (pin "2") (pinfunction "S_2") (pintype "unspecified"))
      (node (ref "R3") (pin "1") (pinfunction "1_1") (pintype "unspecified"))
      (node (ref "U6") (pin "8") (pinfunction "SCL_8") (pintype "unspecified"))
    )
    (net (code "79") (name "SDA") (class "Default")
      (node (ref "CN7") (pin "3") (pinfunction "SDA_3") (pintype "unspecified"))
      (node (ref "J5") (pin "12") (pinfunction "I2C_SDA_12") (pintype "bidirectional"))
      (node (ref "Q2") (pin "3") (pinfunction "D_3") (pintype "unspecified"))
      (node (ref "Q5") (pin "3") (pinfunction "D_3") (pintype "unspecified"))
      (node (ref "R10") (pin "1") (pinfunction "1_1") (pintype "input"))
      (node (ref "R23") (pin "1") (pinfunction "1_1") (pintype "unspecified"))
      (node (ref "R37") (pin "1") (pinfunction "1_1") (pintype "unspecified"))
      (node (ref "R9") (pin "2") (pinfunction "2_2") (pintype "unspecified"))
      (node (ref "U10") (pin "3") (pinfunction "3_3") (pintype "unspecified"))
    )
    (net (code "80") (name "SDA1") (class "Default")
      (node (ref "CN8") (pin "3") (pinfunction "SDA_3") (pintype "unspecified"))
      (node (ref "J5") (pin "51") (pinfunction "I2C_SDA1_51") (pintype "bidirectional"))
      (node (ref "U9") (pin "2") (pinfunction "2_2") (pintype "unspecified"))
    )
    (net (code "81") (name "SDA_1.8V") (class "Default")
      (node (ref "Q5") (pin "2") (pinfunction "S_2") (pintype "unspecified"))
      (node (ref "R25") (pin "1") (pinfunction "1_1") (pintype "unspecified"))
      (node (ref "U7") (pin "24") (pinfunction "SDA/SDI_24") (pintype "unspecified"))
    )
    (net (code "82") (name "SDA_3.3V") (class "Default")
      (node (ref "Q2") (pin "2") (pinfunction "S_2") (pintype "unspecified"))
      (node (ref "R7") (pin "2") (pinfunction "2_2") (pintype "unspecified"))
      (node (ref "U6") (pin "7") (pinfunction "SDA_7") (pintype "unspecified"))
    )
    (net (code "83") (name "SDO{slash}ADR_1.8V") (class "Default")
      (node (ref "Q3") (pin "2") (pinfunction "S_2") (pintype "unspecified"))
      (node (ref "R20") (pin "1") (pinfunction "1_1") (pintype "unspecified"))
      (node (ref "U7") (pin "9") (pinfunction "SDO/AD0_9") (pintype "unspecified"))
    )
    (net (code "84") (name "SWDCK") (class "Default")
      (node (ref "J5") (pin "21") (pinfunction "SWDCK_21") (pintype "bidirectional"))
      (node (ref "P6") (pin "4") (pinfunction "4_4") (pintype "input"))
    )
    (net (code "85") (name "SWDIO") (class "Default")
      (node (ref "J5") (pin "23") (pinfunction "SWDIO_23") (pintype "bidirectional"))
      (node (ref "P6") (pin "2") (pinfunction "2_2") (pintype "input"))
    )
    (net (code "86") (name "TX1") (class "Default")
      (node (ref "J5") (pin "17") (pinfunction "TX1_17") (pintype "bidirectional"))
      (node (ref "JP2") (pin "3") (pinfunction "DIN_3") (pintype "input"))
      (node (ref "U3") (pin "8") (pinfunction "8_8") (pintype "unspecified"))
    )
    (net (code "87") (name "TX2") (class "Default")
      (node (ref "J5") (pin "22") (pinfunction "TX2_22") (pintype "bidirectional"))
      (node (ref "R30") (pin "2") (pinfunction "2_2") (pintype "input"))
      (node (ref "U4") (pin "4") (pinfunction "4_4") (pintype "unspecified"))
    )
    (net (code "88") (name "USBHOST_N") (class "Default")
      (node (ref "J5") (pin "37") (pinfunction "USBHOST_D-_37") (pintype "bidirectional"))
    )
    (net (code "89") (name "USBHOST_P") (class "Default")
      (node (ref "J5") (pin "35") (pinfunction "USBHOST_D+_35") (pintype "bidirectional"))
    )
    (net (code "90") (name "USB_N") (class "Default")
      (node (ref "J5") (pin "5") (pinfunction "USB_D-_5") (pintype "bidirectional"))
      (node (ref "R31") (pin "2") (pinfunction "2_2") (pintype "input"))
      (node (ref "USBC1") (pin "A7") (pinfunction "DN1_A7") (pintype "unspecified"))
      (node (ref "USBC1") (pin "B7") (pinfunction "DN2_B7") (pintype "unspecified"))
    )
    (net (code "91") (name "USB_P") (class "Default")
      (node (ref "J5") (pin "3") (pinfunction "USB_D+_3") (pintype "bidirectional"))
      (node (ref "R18") (pin "2") (pinfunction "2_2") (pintype "input"))
      (node (ref "USBC1") (pin "A6") (pinfunction "DP1_A6") (pintype "unspecified"))
      (node (ref "USBC1") (pin "B6") (pinfunction "DP2_B6") (pintype "unspecified"))
    )
    (net (code "92") (name "VCC_RF") (class "Default")
      (node (ref "R27") (pin "1") (pinfunction "1_1") (pintype "input"))
      (node (ref "U18") (pin "9") (pinfunction "VCC_RF_9") (pintype "unspecified"))
    )
    (net (code "93") (name "VIN{slash}3") (class "Default")
      (node (ref "J5") (pin "49") (pinfunction "BATT_VIN/3_49") (pintype "bidirectional"))
    )
    (net (code "94") (name "V_USB") (class "Default")
      (node (ref "F1") (pin "1") (pinfunction "1_1") (pintype "unspecified"))
      (node (ref "USBC1") (pin "A4") (pinfunction "VBUS_A4") (pintype "unspecified"))
      (node (ref "USBC1") (pin "A9") (pinfunction "VBUS_A9") (pintype "unspecified"))
      (node (ref "USBC1") (pin "B4") (pinfunction "VBUS_B4") (pintype "unspecified"))
      (node (ref "USBC1") (pin "B9") (pinfunction "VBUS_B9") (pintype "unspecified"))
    )
    (net (code "95") (name "unconnected-(BOOT-A-Pad1)") (class "Default")
      (node (ref "BOOT") (pin "1") (pinfunction "A_1") (pintype "unspecified+no_connect"))
    )
    (net (code "96") (name "unconnected-(BOOT-C-Pad3)") (class "Default")
      (node (ref "BOOT") (pin "3") (pinfunction "C_3") (pintype "unspecified+no_connect"))
    )
    (net (code "97") (name "unconnected-(JP2-CTS-Pad12)") (class "Default")
      (node (ref "JP2") (pin "12") (pinfunction "CTS_12") (pintype "output+no_connect"))
    )
    (net (code "98") (name "unconnected-(JP2-DIO0-Pad20)") (class "Default")
      (node (ref "JP2") (pin "20") (pinfunction "DIO0_20") (pintype "unspecified+no_connect"))
    )
    (net (code "99") (name "unconnected-(JP2-DIO1-Pad19)") (class "Default")
      (node (ref "JP2") (pin "19") (pinfunction "DIO1_19") (pintype "unspecified+no_connect"))
    )
    (net (code "100") (name "unconnected-(JP2-DIO2-Pad18)") (class "Default")
      (node (ref "JP2") (pin "18") (pinfunction "DIO2_18") (pintype "unspecified+no_connect"))
    )
    (net (code "101") (name "unconnected-(JP2-DIO3-Pad17)") (class "Default")
      (node (ref "JP2") (pin "17") (pinfunction "DIO3_17") (pintype "unspecified+no_connect"))
    )
    (net (code "102") (name "unconnected-(JP2-DIO4-Pad11)") (class "Default")
      (node (ref "JP2") (pin "11") (pinfunction "DIO4_11") (pintype "unspecified+no_connect"))
    )
    (net (code "103") (name "unconnected-(JP2-DIO5-Pad15)") (class "Default")
      (node (ref "JP2") (pin "15") (pinfunction "DIO5_15") (pintype "unspecified+no_connect"))
    )
    (net (code "104") (name "unconnected-(JP2-DIO9-Pad13)") (class "Default")
      (node (ref "JP2") (pin "13") (pinfunction "DIO9_13") (pintype "unspecified+no_connect"))
    )
    (net (code "105") (name "unconnected-(JP2-DIO11-Pad7)") (class "Default")
      (node (ref "JP2") (pin "7") (pinfunction "DIO11_7") (pintype "unspecified+no_connect"))
    )
    (net (code "106") (name "unconnected-(JP2-DIO12-Pad4)") (class "Default")
      (node (ref "JP2") (pin "4") (pinfunction "DIO12_4") (pintype "unspecified+no_connect"))
    )
    (net (code "107") (name "unconnected-(JP2-DTR-Pad9)") (class "Default")
      (node (ref "JP2") (pin "9") (pinfunction "DTR_9") (pintype "unspecified+no_connect"))
    )
    (net (code "108") (name "unconnected-(JP2-RES-Pad8)") (class "Default")
      (node (ref "JP2") (pin "8") (pinfunction "RES_8") (pintype "unspecified+no_connect"))
    )
    (net (code "109") (name "unconnected-(JP2-RES-Pad14)") (class "Default")
      (node (ref "JP2") (pin "14") (pinfunction "RES_14") (pintype "unspecified+no_connect"))
    )
    (net (code "110") (name "unconnected-(JP2-RESET-Pad5)") (class "Default")
      (node (ref "JP2") (pin "5") (pinfunction "RESET_5") (pintype "input+no_connect"))
    )
    (net (code "111") (name "unconnected-(JP2-RSSI-Pad6)") (class "Default")
      (node (ref "JP2") (pin "6") (pinfunction "RSSI_6") (pintype "unspecified+no_connect"))
    )
    (net (code "112") (name "unconnected-(JP2-RTS-Pad16)") (class "Default")
      (node (ref "JP2") (pin "16") (pinfunction "RTS_16") (pintype "input+no_connect"))
    )
    (net (code "113") (name "unconnected-(P6-Pad6)") (class "Default")
      (node (ref "P6") (pin "6") (pinfunction "6_6") (pintype "input+no_connect"))
    )
    (net (code "114") (name "unconnected-(P6-Pad7)") (class "Default")
      (node (ref "P6") (pin "7") (pinfunction "7_7") (pintype "input+no_connect"))
    )
    (net (code "115") (name "unconnected-(P6-Pad8)") (class "Default")
      (node (ref "P6") (pin "8") (pinfunction "8_8") (pintype "input+no_connect"))
    )
    (net (code "116") (name "unconnected-(RESET-A-Pad1)") (class "Default")
      (node (ref "RESET") (pin "1") (pinfunction "A_1") (pintype "unspecified+no_connect"))
    )
    (net (code "117") (name "unconnected-(RESET-C-Pad3)") (class "Default")
      (node (ref "RESET") (pin "3") (pinfunction "C_3") (pintype "unspecified+no_connect"))
    )
    (net (code "118") (name "unconnected-(TF1-CD{slash}DAT32-Pad2)") (class "Default")
      (node (ref "TF1") (pin "2") (pinfunction "CD/DAT32_2") (pintype "unspecified+no_connect"))
    )
    (net (code "119") (name "unconnected-(TF1-DAT2-Pad1)") (class "Default")
      (node (ref "TF1") (pin "1") (pinfunction "DAT2_1") (pintype "unspecified+no_connect"))
    )
    (net (code "120") (name "unconnected-(U6-INT2-Pad5)") (class "Default")
      (node (ref "U6") (pin "5") (pinfunction "INT2_5") (pintype "unspecified+no_connect"))
    )
    (net (code "121") (name "unconnected-(U7-EP-Pad25)") (class "Default")
      (node (ref "U7") (pin "25") (pinfunction "EP_25") (pintype "unspecified+no_connect"))
    )
    (net (code "122") (name "unconnected-(U7-NC-Pad1)") (class "Default")
      (node (ref "U7") (pin "1") (pinfunction "NC_1") (pintype "unspecified+no_connect"))
    )
    (net (code "123") (name "unconnected-(U7-NC-Pad2)") (class "Default")
      (node (ref "U7") (pin "2") (pinfunction "NC_2") (pintype "unspecified+no_connect"))
    )
    (net (code "124") (name "unconnected-(U7-NC-Pad3)") (class "Default")
      (node (ref "U7") (pin "3") (pinfunction "NC_3") (pintype "unspecified+no_connect"))
    )
    (net (code "125") (name "unconnected-(U7-NC-Pad4)") (class "Default")
      (node (ref "U7") (pin "4") (pinfunction "NC_4") (pintype "unspecified+no_connect"))
    )
    (net (code "126") (name "unconnected-(U7-NC-Pad5)") (class "Default")
      (node (ref "U7") (pin "5") (pinfunction "NC_5") (pintype "unspecified+no_connect"))
    )
    (net (code "127") (name "unconnected-(U7-NC-Pad6)") (class "Default")
      (node (ref "U7") (pin "6") (pinfunction "NC_6") (pintype "unspecified+no_connect"))
    )
    (net (code "128") (name "unconnected-(U7-NC-Pad14)") (class "Default")
      (node (ref "U7") (pin "14") (pinfunction "NC_14") (pintype "unspecified+no_connect"))
    )
    (net (code "129") (name "unconnected-(U7-NC-Pad15)") (class "Default")
      (node (ref "U7") (pin "15") (pinfunction "NC_15") (pintype "unspecified+no_connect"))
    )
    (net (code "130") (name "unconnected-(U7-NC-Pad16)") (class "Default")
      (node (ref "U7") (pin "16") (pinfunction "NC_16") (pintype "unspecified+no_connect"))
    )
    (net (code "131") (name "unconnected-(U7-NC-Pad17)") (class "Default")
      (node (ref "U7") (pin "17") (pinfunction "NC_17") (pintype "unspecified+no_connect"))
    )
    (net (code "132") (name "unconnected-(U7-RESV-Pad19)") (class "Default")
      (node (ref "U7") (pin "19") (pinfunction "RESV_19") (pintype "unspecified+no_connect"))
    )
    (net (code "133") (name "unconnected-(U7-RESV-Pad20)") (class "Default")
      (node (ref "U7") (pin "20") (pinfunction "RESV_20") (pintype "unspecified+no_connect"))
    )
    (net (code "134") (name "unconnected-(U12-BYPASS-Pad4)") (class "Default")
      (node (ref "U12") (pin "4") (pinfunction "BYPASS_4") (pintype "unspecified+no_connect"))
    )
    (net (code "135") (name "unconnected-(U18-LNA_EN-Pad14)") (class "Default")
      (node (ref "U18") (pin "14") (pinfunction "LNA_EN_14") (pintype "unspecified+no_connect"))
    )
    (net (code "136") (name "unconnected-(U18-Reserved-Pad15)") (class "Default")
      (node (ref "U18") (pin "15") (pinfunction "Reserved_15") (pintype "unspecified+no_connect"))
    )
    (net (code "137") (name "unconnected-(U18-Reserved-Pad16)") (class "Default")
      (node (ref "U18") (pin "16") (pinfunction "Reserved_16") (pintype "unspecified+no_connect"))
    )
    (net (code "138") (name "unconnected-(U18-Reserved-Pad17)") (class "Default")
      (node (ref "U18") (pin "17") (pinfunction "Reserved_17") (pintype "unspecified+no_connect"))
    )
    (net (code "139") (name "unconnected-(U19-ADJ{slash}NC-Pad3)") (class "Default")
      (node (ref "U19") (pin "3") (pinfunction "ADJ/NC_3") (pintype "unspecified+no_connect"))
    )
    (net (code "140") (name "unconnected-(U19-EXP-Pad9)") (class "Default")
      (node (ref "U19") (pin "9") (pinfunction "EXP_9") (pintype "unspecified+no_connect"))
    )
    (net (code "141") (name "unconnected-(U19-NC-Pad2)") (class "Default")
      (node (ref "U19") (pin "2") (pinfunction "NC_2") (pintype "unspecified+no_connect"))
    )
    (net (code "142") (name "unconnected-(U19-NC-Pad6)") (class "Default")
      (node (ref "U19") (pin "6") (pinfunction "NC_6") (pintype "unspecified+no_connect"))
    )
    (net (code "143") (name "unconnected-(U19-NC-Pad7)") (class "Default")
      (node (ref "U19") (pin "7") (pinfunction "NC_7") (pintype "unspecified+no_connect"))
    )
    (net (code "144") (name "unconnected-(USBC1-SBU1-PadA8)") (class "Default")
      (node (ref "USBC1") (pin "A8") (pinfunction "SBU1_A8") (pintype "unspecified+no_connect"))
    )
    (net (code "145") (name "unconnected-(USBC1-SBU2-PadB8)") (class "Default")
      (node (ref "USBC1") (pin "B8") (pinfunction "SBU2_B8") (pintype "unspecified+no_connect"))
    )
  )
)
